# class_h.net
KiCad netlist of a schematic drawn in EAGLE
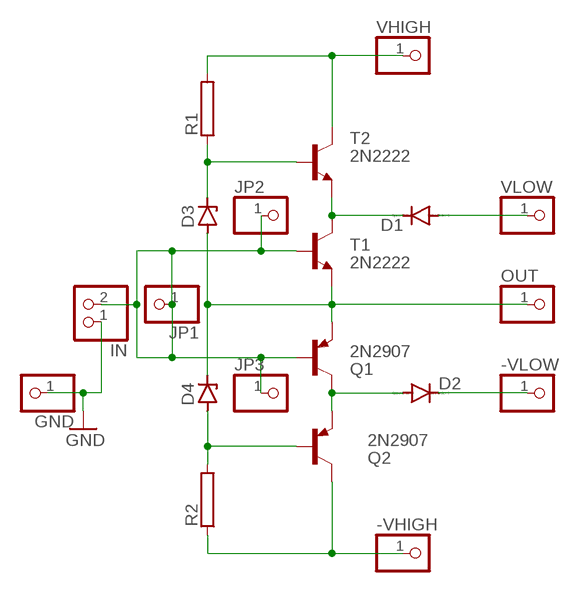
[diagram p0: schematic, sheet 1]

(export (version "E")
  (design (tool "Eeschema 10.0.6"))
  (components
    (comp (ref "-VHIGH")
      (value "PINHD-1X1")
      (footprint "eagle-import:1X01")
      (libsource (lib "eagle-import") (part "PINHD-1X1"))
    )
    (comp (ref "-VLOW")
      (value "PINHD-1X1")
      (footprint "eagle-import:1X01")
      (libsource (lib "eagle-import") (part "PINHD-1X1"))
    )
    (comp (ref "D1")
      (value "1N4148DO35-7")
      (footprint "eagle-import:DO35-7")
      (libsource (lib "eagle-import") (part "1N4148DO35-7"))
    )
    (comp (ref "D2")
      (value "1N4148DO35-7")
      (footprint "eagle-import:DO35-7")
      (libsource (lib "eagle-import") (part "1N4148DO35-7"))
    )
    (comp (ref "D3")
      (value "1N4728")
      (footprint "eagle-import:DO41Z10")
      (libsource (lib "eagle-import") (part "1N4728"))
    )
    (comp (ref "D4")
      (value "1N4728")
      (footprint "eagle-import:DO41Z10")
      (libsource (lib "eagle-import") (part "1N4728"))
    )
    (comp (ref "GND")
      (value "PINHD-1X1")
      (footprint "eagle-import:1X01")
      (libsource (lib "eagle-import") (part "PINHD-1X1"))
    )
    (comp (ref "IN")
      (value "PINHD-1X2")
      (footprint "eagle-import:1X02")
      (libsource (lib "eagle-import") (part "PINHD-1X2"))
    )
    (comp (ref "JP1")
      (value "PINHD-1X1")
      (footprint "eagle-import:1X01")
      (libsource (lib "eagle-import") (part "PINHD-1X1"))
    )
    (comp (ref "JP2")
      (value "PINHD-1X1")
      (footprint "eagle-import:1X01")
      (libsource (lib "eagle-import") (part "PINHD-1X1"))
    )
    (comp (ref "JP3")
      (value "PINHD-1X1")
      (footprint "eagle-import:1X01")
      (libsource (lib "eagle-import") (part "PINHD-1X1"))
    )
    (comp (ref "OUT")
      (value "PINHD-1X1")
      (footprint "eagle-import:1X01")
      (libsource (lib "eagle-import") (part "PINHD-1X1"))
    )
    (comp (ref "Q1")
      (value "2N2907")
      (footprint "eagle-import:TO18")
      (libsource (lib "eagle-import") (part "2N2907"))
    )
    (comp (ref "Q2")
      (value "2N2907")
      (footprint "eagle-import:TO18")
      (libsource (lib "eagle-import") (part "2N2907"))
    )
    (comp (ref "R1")
      (value "RAC01")
      (footprint "eagle-import:AC01")
      (libsource (lib "eagle-import") (part "RAC01"))
    )
    (comp (ref "R2")
      (value "RAC01")
      (footprint "eagle-import:AC01")
      (libsource (lib "eagle-import") (part "RAC01"))
    )
    (comp (ref "T1")
      (value "2N2222")
      (footprint "eagle-import:TO18")
      (libsource (lib "eagle-import") (part "2N2222"))
    )
    (comp (ref "T2")
      (value "2N2222")
      (footprint "eagle-import:TO18")
      (libsource (lib "eagle-import") (part "2N2222"))
    )
    (comp (ref "VHIGH")
      (value "PINHD-1X1")
      (footprint "eagle-import:1X01")
      (libsource (lib "eagle-import") (part "PINHD-1X1"))
    )
    (comp (ref "VLOW")
      (value "PINHD-1X1")
      (footprint "eagle-import:1X01")
      (libsource (lib "eagle-import") (part "PINHD-1X1"))
    )
  )
  (nets
    (net (code "1") (name "GND") (class "Default")
      (node (ref "GND") (pin "1") (pinfunction "1_1") (pintype "passive"))
      (node (ref "IN") (pin "1") (pinfunction "1_1") (pintype "passive"))
    )
    (net (code "2") (name "Net-(-VLOW-Pad1)") (class "Default")
      (node (ref "-VLOW") (pin "1") (pinfunction "1_1") (pintype "passive"))
      (node (ref "D2") (pin "C") (pinfunction "C_C") (pintype "passive"))
    )
    (net (code "3") (name "Net-(D1-PadA)") (class "Default")
      (node (ref "D1") (pin "A") (pinfunction "A_A") (pintype "passive"))
      (node (ref "VLOW") (pin "1") (pinfunction "1_1") (pintype "passive"))
    )
    (net (code "4") (name "Net-(Q1-B)") (class "Default")
      (node (ref "IN") (pin "2") (pinfunction "2_2") (pintype "passive"))
      (node (ref "JP1") (pin "1") (pinfunction "1_1") (pintype "passive"))
      (node (ref "JP2") (pin "1") (pinfunction "1_1") (pintype "passive"))
      (node (ref "JP3") (pin "1") (pinfunction "1_1") (pintype "passive"))
      (node (ref "Q1") (pin "2") (pinfunction "B_2") (pintype "passive"))
      (node (ref "T1") (pin "2") (pinfunction "B_2") (pintype "passive"))
    )
    (net (code "5") (name "Net-(Q1-C)") (class "Default")
      (node (ref "D2") (pin "A") (pinfunction "A_A") (pintype "passive"))
      (node (ref "Q1") (pin "3") (pinfunction "C_3") (pintype "passive"))
      (node (ref "Q2") (pin "1") (pinfunction "E_1") (pintype "passive"))
    )
    (net (code "6") (name "Net-(Q1-E)") (class "Default")
      (node (ref "D3") (pin "A") (pinfunction "A_A") (pintype "passive"))
      (node (ref "D4") (pin "C") (pinfunction "C_C") (pintype "passive"))
      (node (ref "OUT") (pin "1") (pinfunction "1_1") (pintype "passive"))
      (node (ref "Q1") (pin "1") (pinfunction "E_1") (pintype "passive"))
      (node (ref "T1") (pin "1") (pinfunction "E_1") (pintype "passive"))
    )
    (net (code "7") (name "Net-(Q2-B)") (class "Default")
      (node (ref "D4") (pin "A") (pinfunction "A_A") (pintype "passive"))
      (node (ref "Q2") (pin "2") (pinfunction "B_2") (pintype "passive"))
      (node (ref "R2") (pin "2") (pinfunction "2_2") (pintype "passive"))
    )
    (net (code "8") (name "Net-(Q2-C)") (class "Default")
      (node (ref "-VHIGH") (pin "1") (pinfunction "1_1") (pintype "passive"))
      (node (ref "Q2") (pin "3") (pinfunction "C_3") (pintype "passive"))
      (node (ref "R2") (pin "1") (pinfunction "1_1") (pintype "passive"))
    )
    (net (code "9") (name "Net-(T1-C)") (class "Default")
      (node (ref "D1") (pin "C") (pinfunction "C_C") (pintype "passive"))
      (node (ref "T1") (pin "3") (pinfunction "C_3") (pintype "passive"))
      (node (ref "T2") (pin "1") (pinfunction "E_1") (pintype "passive"))
    )
    (net (code "10") (name "Net-(T2-B)") (class "Default")
      (node (ref "D3") (pin "C") (pinfunction "C_C") (pintype "passive"))
      (node (ref "R1") (pin "1") (pinfunction "1_1") (pintype "passive"))
      (node (ref "T2") (pin "2") (pinfunction "B_2") (pintype "passive"))
    )
    (net (code "11") (name "Net-(T2-C)") (class "Default")
      (node (ref "R1") (pin "2") (pinfunction "2_2") (pintype "passive"))
      (node (ref "T2") (pin "3") (pinfunction "C_3") (pintype "passive"))
      (node (ref "VHIGH") (pin "1") (pinfunction "1_1") (pintype "passive"))
    )
  )
)
